# Hardwiring.net
KiCad netlist of a schematic drawn in Altium Designer
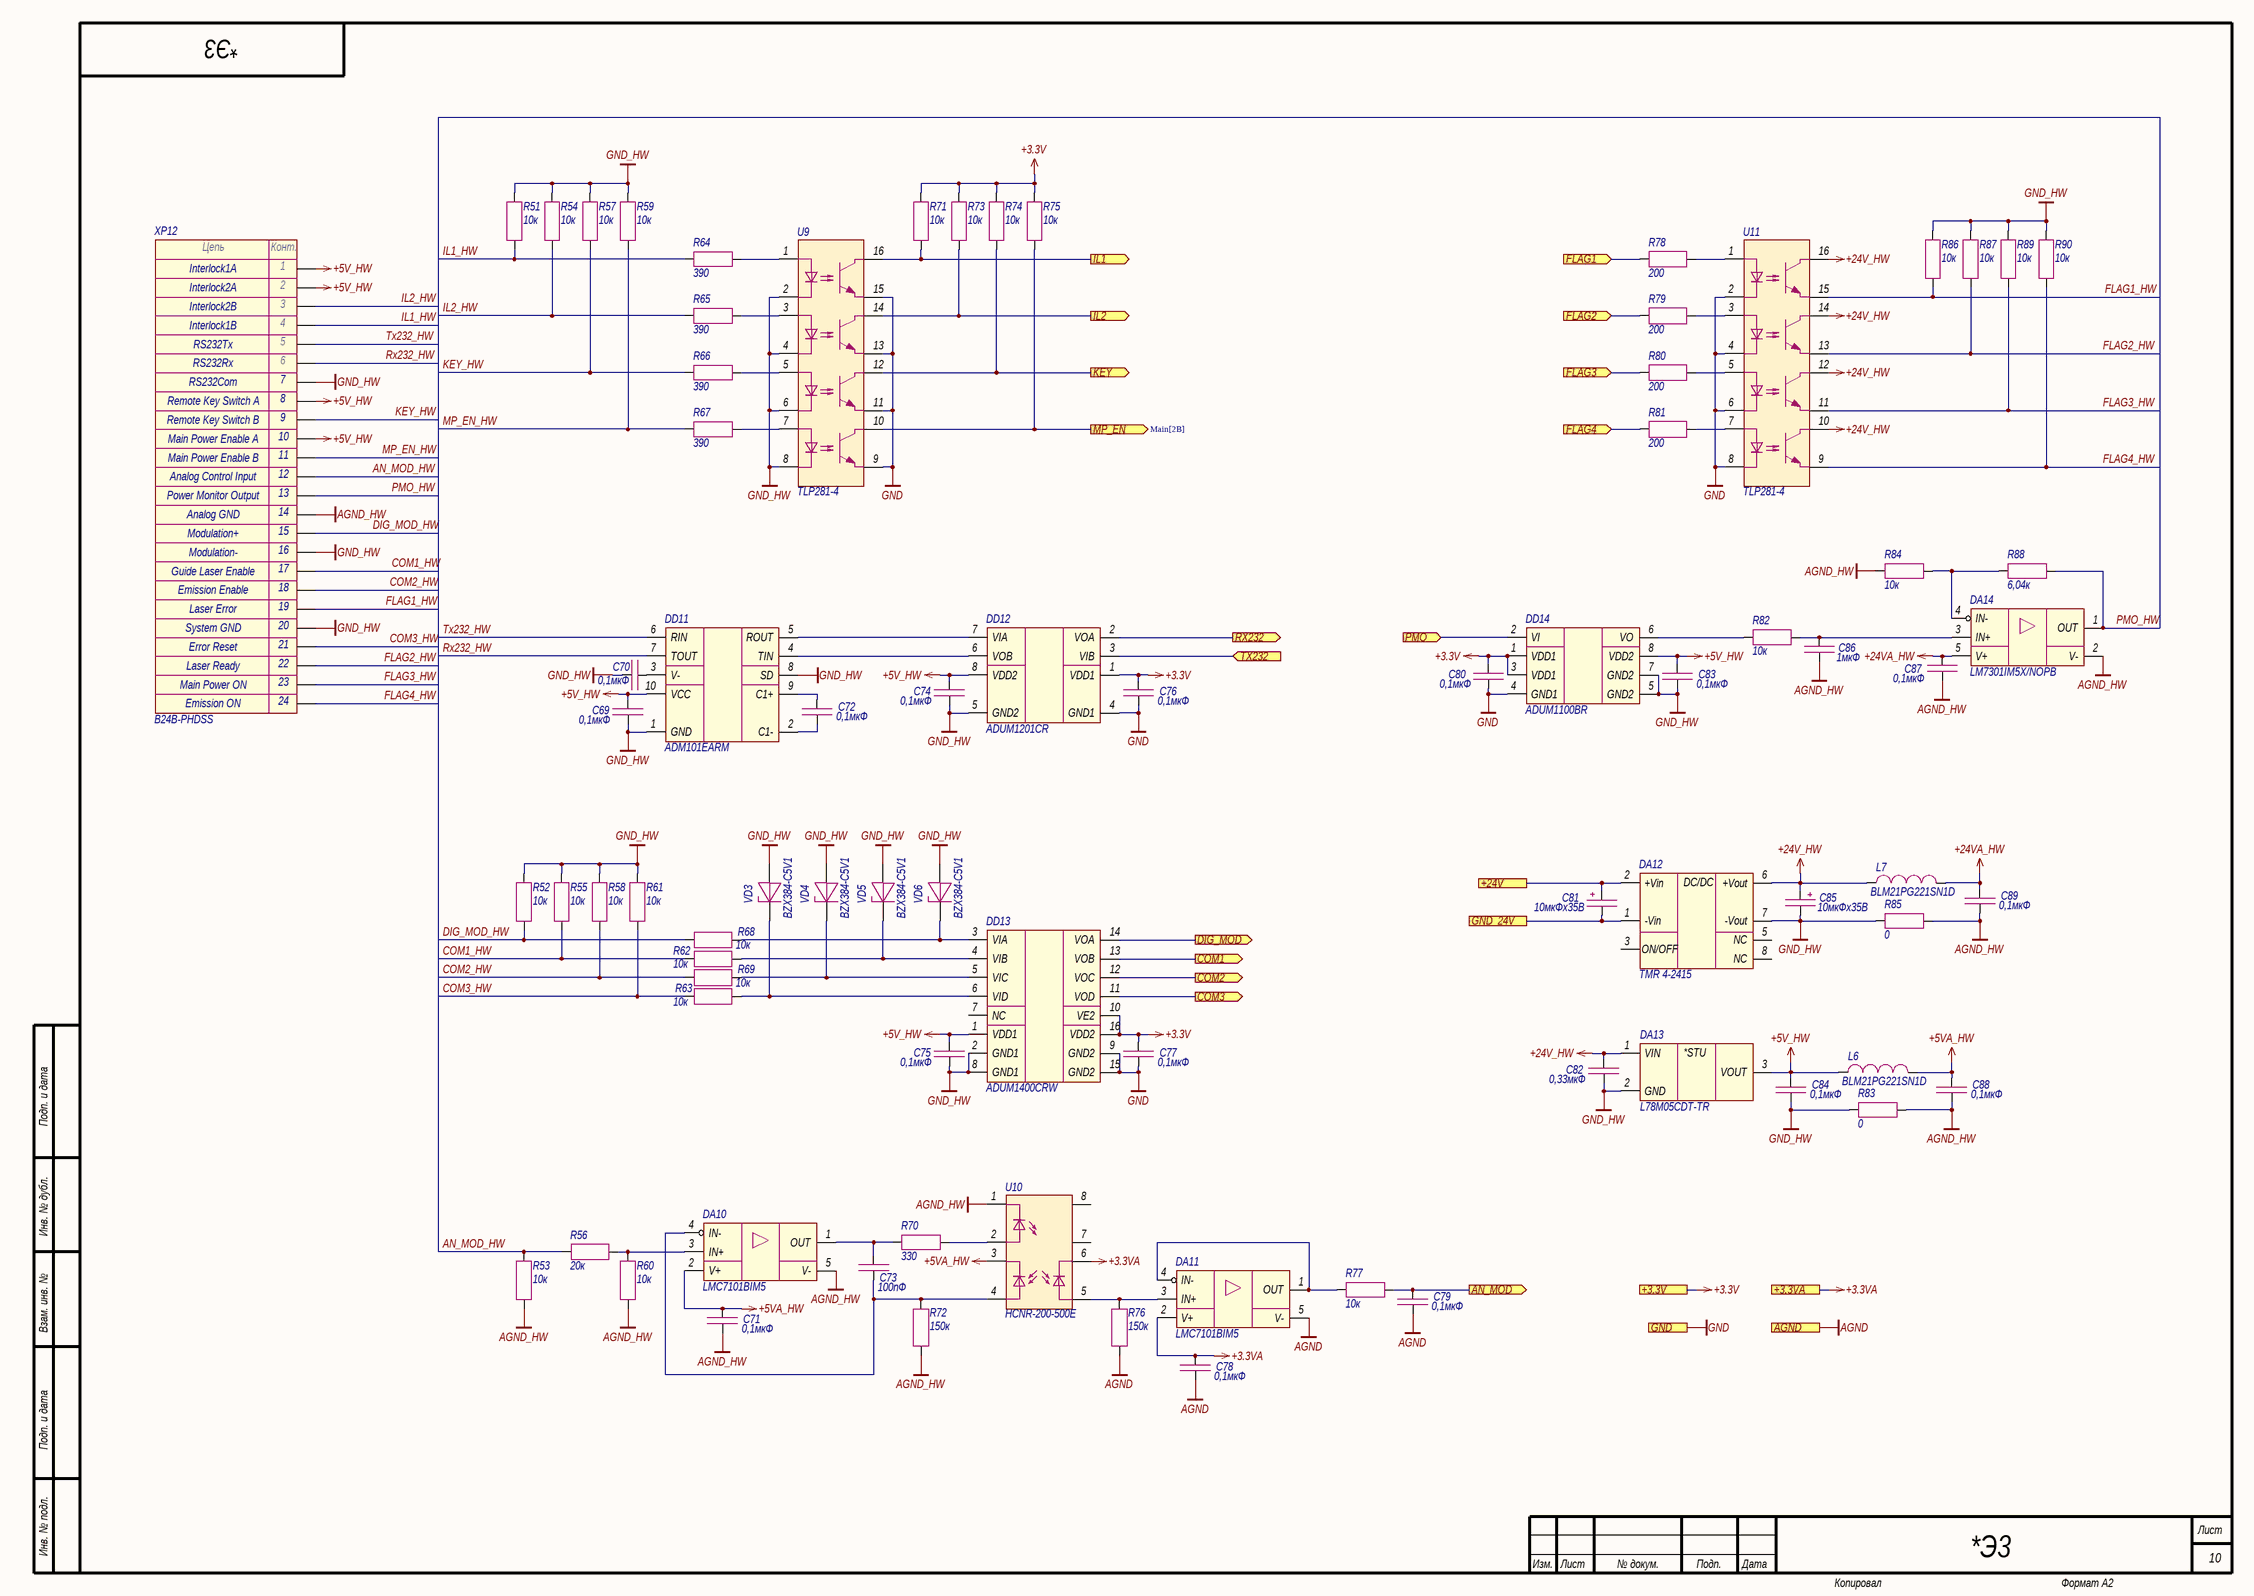
[diagram p0: Hardwiring.SchDoc]

(export (version "E")
  (design (tool "Eeschema 10.0.6"))
  (components
    (comp (ref "C69")
      (value "0,1мкФ")
      (footprint "Pcb_library:CAP_0603")
      (fields (field (name "MANUFACTURER") "Murata"))
      (libsource (lib "Schem_library") (part "Capacitor"))
    )
    (comp (ref "C70")
      (value "0,1мкФ")
      (footprint "Pcb_library:CAP_0603")
      (fields (field (name "MANUFACTURER") "Murata"))
      (libsource (lib "Schem_library") (part "Capacitor"))
    )
    (comp (ref "C71")
      (value "0,1мкФ")
      (footprint "Pcb_library:CAP_0603")
      (fields (field (name "MANUFACTURER") "Murata"))
      (libsource (lib "Schem_library") (part "Capacitor"))
    )
    (comp (ref "C72")
      (value "0,1мкФ")
      (footprint "Pcb_library:CAP_0603")
      (fields (field (name "MANUFACTURER") "Murata"))
      (libsource (lib "Schem_library") (part "Capacitor"))
    )
    (comp (ref "C73")
      (value "100пФ")
      (footprint "Pcb_library:CAP_0603")
      (fields (field (name "MANUFACTURER") "Murata"))
      (libsource (lib "Schem_library") (part "Capacitor"))
    )
    (comp (ref "C74")
      (value "0,1мкФ")
      (footprint "Pcb_library:CAP_0603")
      (fields (field (name "MANUFACTURER") "Murata"))
      (libsource (lib "Schem_library") (part "Capacitor"))
    )
    (comp (ref "C75")
      (value "0,1мкФ")
      (footprint "Pcb_library:CAP_0603")
      (fields (field (name "MANUFACTURER") "Murata"))
      (libsource (lib "Schem_library") (part "Capacitor"))
    )
    (comp (ref "C76")
      (value "0,1мкФ")
      (footprint "Pcb_library:CAP_0603")
      (fields (field (name "MANUFACTURER") "Murata"))
      (libsource (lib "Schem_library") (part "Capacitor"))
    )
    (comp (ref "C77")
      (value "0,1мкФ")
      (footprint "Pcb_library:CAP_0603")
      (fields (field (name "MANUFACTURER") "Murata"))
      (libsource (lib "Schem_library") (part "Capacitor"))
    )
    (comp (ref "C78")
      (value "0,1мкФ")
      (footprint "Pcb_library:CAP_0603")
      (fields (field (name "MANUFACTURER") "Murata"))
      (libsource (lib "Schem_library") (part "Capacitor"))
    )
    (comp (ref "C79")
      (value "0,1мкФ")
      (footprint "Pcb_library:CAP_0603")
      (fields (field (name "MANUFACTURER") "Murata"))
      (libsource (lib "Schem_library") (part "Capacitor"))
    )
    (comp (ref "C80")
      (value "0,1мкФ")
      (footprint "Pcb_library:CAP_0603")
      (fields (field (name "MANUFACTURER") "Murata"))
      (libsource (lib "Schem_library") (part "Capacitor"))
    )
    (comp (ref "C81")
      (value "10мкФх35B")
      (footprint "Pcb_library:CAP_C")
      (libsource (lib "Schem_library") (part "Capacitor_Polar"))
    )
    (comp (ref "C82")
      (value "0,33мкФ")
      (footprint "Pcb_library:CAP_0805")
      (fields (field (name "MANUFACTURER") "Murata"))
      (libsource (lib "Schem_library") (part "Capacitor"))
    )
    (comp (ref "C83")
      (value "0,1мкФ")
      (footprint "Pcb_library:CAP_0603")
      (fields (field (name "MANUFACTURER") "Murata"))
      (libsource (lib "Schem_library") (part "Capacitor"))
    )
    (comp (ref "C84")
      (value "0,1мкФ")
      (footprint "Pcb_library:CAP_0603")
      (fields (field (name "MANUFACTURER") "Murata"))
      (libsource (lib "Schem_library") (part "Capacitor"))
    )
    (comp (ref "C85")
      (value "10мкФх35B")
      (footprint "Pcb_library:CAP_C")
      (libsource (lib "Schem_library") (part "Capacitor_Polar"))
    )
    (comp (ref "C86")
      (value "1мкФ")
      (footprint "Pcb_library:CAP_0603")
      (fields (field (name "MANUFACTURER") "Murata"))
      (libsource (lib "Schem_library") (part "Capacitor"))
    )
    (comp (ref "C87")
      (value "0,1мкФ")
      (footprint "Pcb_library:CAP_0603")
      (fields (field (name "MANUFACTURER") "Murata"))
      (libsource (lib "Schem_library") (part "Capacitor"))
    )
    (comp (ref "C88")
      (value "0,1мкФ")
      (footprint "Pcb_library:CAP_0603")
      (fields (field (name "MANUFACTURER") "Murata"))
      (libsource (lib "Schem_library") (part "Capacitor"))
    )
    (comp (ref "C89")
      (value "0,1мкФ")
      (footprint "Pcb_library:CAP_0603")
      (fields (field (name "MANUFACTURER") "Murata"))
      (libsource (lib "Schem_library") (part "Capacitor"))
    )
    (comp (ref "DA10")
      (value "LMC7101BIM5")
      (footprint "Pcb_library:SOT-23-5")
      (fields (field (name "MANUFACTURER") "Texas Instruments"))
      (libsource (lib "Schem_library") (part "LMC7101"))
    )
    (comp (ref "DA11")
      (value "LMC7101BIM5")
      (footprint "Pcb_library:SOT-23-5")
      (fields (field (name "MANUFACTURER") "Texas Instruments"))
      (libsource (lib "Schem_library") (part "LMC7101"))
    )
    (comp (ref "DA12")
      (value "TMR 4-2415")
      (footprint "Pcb_library:TMR4 (SIP-8)")
      (fields (field (name "MANUFACTURER") "Traco Power"))
      (libsource (lib "Schem_library") (part "TMR4"))
    )
    (comp (ref "DA13")
      (value "L78M05CDT-TR")
      (footprint "Pcb_library:TO-252")
      (fields (field (name "MANUFACTURER") "STMicroelectronics"))
      (libsource (lib "Schem_library") (part "L78M"))
    )
    (comp (ref "DA14")
      (value "LM7301IM5X/NOPB")
      (footprint "Pcb_library:SOT-23-5")
      (fields (field (name "MANUFACTURER") "Texas Instruments"))
      (libsource (lib "Schem_library") (part "LM7301IM5"))
    )
    (comp (ref "DD11")
      (value "ADM101EARM")
      (footprint "Pcb_library:MSOP-10")
      (fields (field (name "MANUFACTURER") "Analog Devices"))
      (libsource (lib "Schem_library") (part "ADM101EARM"))
    )
    (comp (ref "DD12")
      (value "ADUM1201CR")
      (footprint "Pcb_library:SOIC-8")
      (fields (field (name "MANUFACTURER") "Analog Devices"))
      (libsource (lib "Schem_library") (part "ADUM1201"))
    )
    (comp (ref "DD13")
      (value "ADUM1400CRW")
      (footprint "Pcb_library:SOIC-16W")
      (fields (field (name "MANUFACTURER") "Analog Devices"))
      (libsource (lib "Schem_library") (part "ADUM1400"))
    )
    (comp (ref "DD14")
      (value "ADUM1100BR")
      (footprint "Pcb_library:SOIC-8")
      (fields (field (name "MANUFACTURER") "Analog Devices"))
      (libsource (lib "Schem_library") (part "ADUM1100"))
    )
    (comp (ref "L6")
      (value "BLM21PG221SN1D")
      (footprint "Pcb_library:IND_0805")
      (fields (field (name "MANUFACTURER") "Murata"))
      (libsource (lib "Schem_library") (part "Inductor"))
    )
    (comp (ref "L7")
      (value "BLM21PG221SN1D")
      (footprint "Pcb_library:IND_0805")
      (fields (field (name "MANUFACTURER") "Murata"))
      (libsource (lib "Schem_library") (part "Inductor"))
    )
    (comp (ref "R51")
      (value "10к")
      (footprint "Pcb_library:RES_0603")
      (fields (field (name "MANUFACTURER") "Yageo"))
      (libsource (lib "Schem_library") (part "Resistor"))
    )
    (comp (ref "R52")
      (value "10к")
      (footprint "Pcb_library:RES_0603")
      (fields (field (name "MANUFACTURER") "Yageo"))
      (libsource (lib "Schem_library") (part "Resistor"))
    )
    (comp (ref "R53")
      (value "10к")
      (footprint "Pcb_library:RES_0603")
      (fields (field (name "MANUFACTURER") "Yageo"))
      (libsource (lib "Schem_library") (part "Resistor"))
    )
    (comp (ref "R54")
      (value "10к")
      (footprint "Pcb_library:RES_0603")
      (fields (field (name "MANUFACTURER") "Yageo"))
      (libsource (lib "Schem_library") (part "Resistor"))
    )
    (comp (ref "R55")
      (value "10к")
      (footprint "Pcb_library:RES_0603")
      (fields (field (name "MANUFACTURER") "Yageo"))
      (libsource (lib "Schem_library") (part "Resistor"))
    )
    (comp (ref "R56")
      (value "20к")
      (footprint "Pcb_library:RES_0603")
      (fields (field (name "MANUFACTURER") "Yageo"))
      (libsource (lib "Schem_library") (part "Resistor"))
    )
    (comp (ref "R57")
      (value "10к")
      (footprint "Pcb_library:RES_0603")
      (fields (field (name "MANUFACTURER") "Yageo"))
      (libsource (lib "Schem_library") (part "Resistor"))
    )
    (comp (ref "R58")
      (value "10к")
      (footprint "Pcb_library:RES_0603")
      (fields (field (name "MANUFACTURER") "Yageo"))
      (libsource (lib "Schem_library") (part "Resistor"))
    )
    (comp (ref "R59")
      (value "10к")
      (footprint "Pcb_library:RES_0603")
      (fields (field (name "MANUFACTURER") "Yageo"))
      (libsource (lib "Schem_library") (part "Resistor"))
    )
    (comp (ref "R60")
      (value "10к")
      (footprint "Pcb_library:RES_0603")
      (fields (field (name "MANUFACTURER") "Yageo"))
      (libsource (lib "Schem_library") (part "Resistor"))
    )
    (comp (ref "R61")
      (value "10к")
      (footprint "Pcb_library:RES_0603")
      (fields (field (name "MANUFACTURER") "Yageo"))
      (libsource (lib "Schem_library") (part "Resistor"))
    )
    (comp (ref "R62")
      (value "10к")
      (footprint "Pcb_library:RES_0603")
      (fields (field (name "MANUFACTURER") "Yageo"))
      (libsource (lib "Schem_library") (part "Resistor"))
    )
    (comp (ref "R63")
      (value "10к")
      (footprint "Pcb_library:RES_0603")
      (fields (field (name "MANUFACTURER") "Yageo"))
      (libsource (lib "Schem_library") (part "Resistor"))
    )
    (comp (ref "R64")
      (value "390")
      (footprint "Pcb_library:RES_0603")
      (fields (field (name "MANUFACTURER") "Yageo"))
      (libsource (lib "Schem_library") (part "Resistor"))
    )
    (comp (ref "R65")
      (value "390")
      (footprint "Pcb_library:RES_0603")
      (fields (field (name "MANUFACTURER") "Yageo"))
      (libsource (lib "Schem_library") (part "Resistor"))
    )
    (comp (ref "R66")
      (value "390")
      (footprint "Pcb_library:RES_0603")
      (fields (field (name "MANUFACTURER") "Yageo"))
      (libsource (lib "Schem_library") (part "Resistor"))
    )
    (comp (ref "R67")
      (value "390")
      (footprint "Pcb_library:RES_0603")
      (fields (field (name "MANUFACTURER") "Yageo"))
      (libsource (lib "Schem_library") (part "Resistor"))
    )
    (comp (ref "R68")
      (value "10к")
      (footprint "Pcb_library:RES_0603")
      (fields (field (name "MANUFACTURER") "Yageo"))
      (libsource (lib "Schem_library") (part "Resistor"))
    )
    (comp (ref "R69")
      (value "10к")
      (footprint "Pcb_library:RES_0603")
      (fields (field (name "MANUFACTURER") "Yageo"))
      (libsource (lib "Schem_library") (part "Resistor"))
    )
    (comp (ref "R70")
      (value "330")
      (footprint "Pcb_library:RES_0603")
      (fields (field (name "MANUFACTURER") "Yageo"))
      (libsource (lib "Schem_library") (part "Resistor"))
    )
    (comp (ref "R71")
      (value "10к")
      (footprint "Pcb_library:RES_0603")
      (fields (field (name "MANUFACTURER") "Yageo"))
      (libsource (lib "Schem_library") (part "Resistor"))
    )
    (comp (ref "R72")
      (value "150к")
      (footprint "Pcb_library:RES_0603")
      (fields (field (name "MANUFACTURER") "Yageo"))
      (libsource (lib "Schem_library") (part "Resistor"))
    )
    (comp (ref "R73")
      (value "10к")
      (footprint "Pcb_library:RES_0603")
      (fields (field (name "MANUFACTURER") "Yageo"))
      (libsource (lib "Schem_library") (part "Resistor"))
    )
    (comp (ref "R74")
      (value "10к")
      (footprint "Pcb_library:RES_0603")
      (fields (field (name "MANUFACTURER") "Yageo"))
      (libsource (lib "Schem_library") (part "Resistor"))
    )
    (comp (ref "R75")
      (value "10к")
      (footprint "Pcb_library:RES_0603")
      (fields (field (name "MANUFACTURER") "Yageo"))
      (libsource (lib "Schem_library") (part "Resistor"))
    )
    (comp (ref "R76")
      (value "150к")
      (footprint "Pcb_library:RES_0603")
      (fields (field (name "MANUFACTURER") "Yageo"))
      (libsource (lib "Schem_library") (part "Resistor"))
    )
    (comp (ref "R77")
      (value "10к")
      (footprint "Pcb_library:RES_0603")
      (fields (field (name "MANUFACTURER") "Yageo"))
      (libsource (lib "Schem_library") (part "Resistor"))
    )
    (comp (ref "R78")
      (value "200")
      (footprint "Pcb_library:RES_0603")
      (fields (field (name "MANUFACTURER") "Yageo"))
      (libsource (lib "Schem_library") (part "Resistor"))
    )
    (comp (ref "R79")
      (value "200")
      (footprint "Pcb_library:RES_0603")
      (fields (field (name "MANUFACTURER") "Yageo"))
      (libsource (lib "Schem_library") (part "Resistor"))
    )
    (comp (ref "R80")
      (value "200")
      (footprint "Pcb_library:RES_0603")
      (fields (field (name "MANUFACTURER") "Yageo"))
      (libsource (lib "Schem_library") (part "Resistor"))
    )
    (comp (ref "R81")
      (value "200")
      (footprint "Pcb_library:RES_0603")
      (fields (field (name "MANUFACTURER") "Yageo"))
      (libsource (lib "Schem_library") (part "Resistor"))
    )
    (comp (ref "R82")
      (value "10к")
      (footprint "Pcb_library:RES_0603")
      (fields (field (name "MANUFACTURER") "Yageo"))
      (libsource (lib "Schem_library") (part "Resistor"))
    )
    (comp (ref "R83")
      (value "0")
      (footprint "Pcb_library:RES_0805")
      (fields (field (name "MANUFACTURER") "Yageo"))
      (libsource (lib "Schem_library") (part "Resistor"))
    )
    (comp (ref "R84")
      (value "10к")
      (footprint "Pcb_library:RES_0603")
      (fields (field (name "MANUFACTURER") "Yageo"))
      (libsource (lib "Schem_library") (part "Resistor"))
    )
    (comp (ref "R85")
      (value "0")
      (footprint "Pcb_library:RES_0805")
      (fields (field (name "MANUFACTURER") "Yageo"))
      (libsource (lib "Schem_library") (part "Resistor"))
    )
    (comp (ref "R86")
      (value "10к")
      (footprint "Pcb_library:RES_0603")
      (fields (field (name "MANUFACTURER") "Yageo"))
      (libsource (lib "Schem_library") (part "Resistor"))
    )
    (comp (ref "R87")
      (value "10к")
      (footprint "Pcb_library:RES_0603")
      (fields (field (name "MANUFACTURER") "Yageo"))
      (libsource (lib "Schem_library") (part "Resistor"))
    )
    (comp (ref "R88")
      (value "6,04к")
      (footprint "Pcb_library:RES_0603")
      (fields (field (name "MANUFACTURER") "Yageo"))
      (libsource (lib "Schem_library") (part "Resistor"))
    )
    (comp (ref "R89")
      (value "10к")
      (footprint "Pcb_library:RES_0603")
      (fields (field (name "MANUFACTURER") "Yageo"))
      (libsource (lib "Schem_library") (part "Resistor"))
    )
    (comp (ref "R90")
      (value "10к")
      (footprint "Pcb_library:RES_0603")
      (fields (field (name "MANUFACTURER") "Yageo"))
      (libsource (lib "Schem_library") (part "Resistor"))
    )
    (comp (ref "U9")
      (value "TLP281-4")
      (footprint "Pcb_library:SOP-16")
      (fields (field (name "MANUFACTURER") "Toshiba"))
      (libsource (lib "Schem_library") (part "TLP281-4"))
    )
    (comp (ref "U10")
      (value "HCNR-200-500E")
      (footprint "Pcb_library:HCNR200")
      (fields (field (name "MANUFACTURER") "Avago"))
      (libsource (lib "Schem_library") (part "HCNR200"))
    )
    (comp (ref "U11")
      (value "TLP281-4")
      (footprint "Pcb_library:SOP-16")
      (fields (field (name "MANUFACTURER") "Toshiba"))
      (libsource (lib "Schem_library") (part "TLP281-4"))
    )
    (comp (ref "VD3")
      (value "BZX384-C5V1")
      (footprint "Pcb_library:SOD-323")
      (fields (field (name "MANUFACTURER") "Nexperia"))
      (libsource (lib "Schem_library") (part "Diode_Zener"))
    )
    (comp (ref "VD4")
      (value "BZX384-C5V1")
      (footprint "Pcb_library:SOD-323")
      (fields (field (name "MANUFACTURER") "Nexperia"))
      (libsource (lib "Schem_library") (part "Diode_Zener"))
    )
    (comp (ref "VD5")
      (value "BZX384-C5V1")
      (footprint "Pcb_library:SOD-323")
      (fields (field (name "MANUFACTURER") "Nexperia"))
      (libsource (lib "Schem_library") (part "Diode_Zener"))
    )
    (comp (ref "VD6")
      (value "BZX384-C5V1")
      (footprint "Pcb_library:SOD-323")
      (fields (field (name "MANUFACTURER") "Nexperia"))
      (libsource (lib "Schem_library") (part "Diode_Zener"))
    )
    (comp (ref "XP12")
      (value "B24B-PHDSS")
      (footprint "Pcb_library:B24B-PHDSS")
      (fields (field (name "MANUFACTURER") "JST"))
      (libsource (lib "Schem_library") (part "Connector-24"))
    )
  )
  (nets
    (net (code "1") (name "+3.3V") (class "Default")
      (node (ref "C76") (pin "1") (pinfunction "1_1") (pintype "passive"))
      (node (ref "C77") (pin "1") (pinfunction "1_1") (pintype "passive"))
      (node (ref "C80") (pin "1") (pinfunction "1_1") (pintype "passive"))
      (node (ref "DD12") (pin "1") (pinfunction "VDD1_1") (pintype "passive"))
      (node (ref "DD13") (pin "10") (pinfunction "VE2_10") (pintype "passive"))
      (node (ref "DD13") (pin "16") (pinfunction "VDD2_16") (pintype "passive"))
      (node (ref "DD14") (pin "1") (pinfunction "VDD1_1") (pintype "passive"))
      (node (ref "DD14") (pin "3") (pinfunction "VDD1_3") (pintype "passive"))
      (node (ref "R71") (pin "1") (pinfunction "1_1") (pintype "passive"))
      (node (ref "R73") (pin "1") (pinfunction "1_1") (pintype "passive"))
      (node (ref "R74") (pin "1") (pinfunction "1_1") (pintype "passive"))
      (node (ref "R75") (pin "1") (pinfunction "1_1") (pintype "passive"))
    )
    (net (code "2") (name "+3.3VA") (class "Default")
      (node (ref "C78") (pin "1") (pinfunction "1_1") (pintype "passive"))
      (node (ref "DA11") (pin "2") (pinfunction "V+_2") (pintype "passive"))
      (node (ref "U10") (pin "6") (pintype "passive"))
    )
    (net (code "3") (name "+5VA_HW") (class "Default")
      (node (ref "C71") (pin "1") (pinfunction "1_1") (pintype "passive"))
      (node (ref "C88") (pin "1") (pinfunction "1_1") (pintype "passive"))
      (node (ref "DA10") (pin "2") (pinfunction "V+_2") (pintype "passive"))
      (node (ref "L6") (pin "2") (pinfunction "2_2") (pintype "passive"))
      (node (ref "U10") (pin "3") (pintype "passive"))
    )
    (net (code "4") (name "+5V_HW") (class "Default")
      (node (ref "C69") (pin "1") (pinfunction "1_1") (pintype "passive"))
      (node (ref "C74") (pin "1") (pinfunction "1_1") (pintype "passive"))
      (node (ref "C75") (pin "1") (pinfunction "1_1") (pintype "passive"))
      (node (ref "C83") (pin "1") (pinfunction "1_1") (pintype "passive"))
      (node (ref "C84") (pin "1") (pinfunction "1_1") (pintype "passive"))
      (node (ref "DA13") (pin "3") (pinfunction "VOUT_3") (pintype "passive"))
      (node (ref "DD11") (pin "10") (pinfunction "VCC_10") (pintype "passive"))
      (node (ref "DD12") (pin "8") (pinfunction "VDD2_8") (pintype "passive"))
      (node (ref "DD13") (pin "1") (pinfunction "VDD1_1") (pintype "passive"))
      (node (ref "DD14") (pin "8") (pinfunction "VDD2_8") (pintype "passive"))
      (node (ref "L6") (pin "1") (pinfunction "1_1") (pintype "passive"))
      (node (ref "XP12") (pin "1") (pintype "passive"))
      (node (ref "XP12") (pin "10") (pintype "passive"))
      (node (ref "XP12") (pin "2") (pintype "passive"))
      (node (ref "XP12") (pin "8") (pintype "passive"))
    )
    (net (code "5") (name "+24VA_HW") (class "Default")
      (node (ref "C87") (pin "1") (pinfunction "1_1") (pintype "passive"))
      (node (ref "C89") (pin "1") (pinfunction "1_1") (pintype "passive"))
      (node (ref "DA14") (pin "5") (pinfunction "V+_5") (pintype "passive"))
      (node (ref "L7") (pin "2") (pinfunction "2_2") (pintype "passive"))
    )
    (net (code "6") (name "+24V_HW") (class "Default")
      (node (ref "C82") (pin "2") (pinfunction "2_2") (pintype "passive"))
      (node (ref "C85") (pin "1") (pinfunction "1_1") (pintype "passive"))
      (node (ref "DA12") (pin "6") (pinfunction "+Vout_6") (pintype "passive"))
      (node (ref "DA13") (pin "1") (pinfunction "VIN_1") (pintype "passive"))
      (node (ref "L7") (pin "1") (pinfunction "1_1") (pintype "passive"))
      (node (ref "U11") (pin "10") (pintype "passive"))
      (node (ref "U11") (pin "12") (pintype "passive"))
      (node (ref "U11") (pin "14") (pintype "passive"))
      (node (ref "U11") (pin "16") (pintype "passive"))
    )
    (net (code "7") (name "/+24V") (class "Default")
      (node (ref "C81") (pin "1") (pinfunction "1_1") (pintype "passive"))
      (node (ref "DA12") (pin "2") (pinfunction "+Vin_2") (pintype "passive"))
    )
    (net (code "8") (name "/AN_MOD") (class "Default")
      (node (ref "C79") (pin "1") (pinfunction "1_1") (pintype "passive"))
      (node (ref "R77") (pin "2") (pinfunction "2_2") (pintype "passive"))
    )
    (net (code "9") (name "/AN_MOD_HW") (class "Default")
      (node (ref "R53") (pin "1") (pinfunction "1_1") (pintype "passive"))
      (node (ref "R56") (pin "1") (pinfunction "1_1") (pintype "passive"))
      (node (ref "XP12") (pin "12") (pintype "passive"))
    )
    (net (code "10") (name "/COM1") (class "Default")
      (node (ref "DD13") (pin "13") (pinfunction "VOB_13") (pintype "passive"))
    )
    (net (code "11") (name "/COM1_HW") (class "Default")
      (node (ref "R55") (pin "2") (pinfunction "2_2") (pintype "passive"))
      (node (ref "R62") (pin "1") (pinfunction "1_1") (pintype "passive"))
      (node (ref "XP12") (pin "17") (pintype "passive"))
    )
    (net (code "12") (name "/COM2") (class "Default")
      (node (ref "DD13") (pin "12") (pinfunction "VOC_12") (pintype "passive"))
    )
    (net (code "13") (name "/COM2_HW") (class "Default")
      (node (ref "R58") (pin "2") (pinfunction "2_2") (pintype "passive"))
      (node (ref "R69") (pin "1") (pinfunction "1_1") (pintype "passive"))
      (node (ref "XP12") (pin "18") (pintype "passive"))
    )
    (net (code "14") (name "/COM3") (class "Default")
      (node (ref "DD13") (pin "11") (pinfunction "VOD_11") (pintype "passive"))
    )
    (net (code "15") (name "/COM3_HW") (class "Default")
      (node (ref "R61") (pin "2") (pinfunction "2_2") (pintype "passive"))
      (node (ref "R63") (pin "1") (pinfunction "1_1") (pintype "passive"))
      (node (ref "XP12") (pin "21") (pintype "passive"))
    )
    (net (code "16") (name "/DIG_MOD") (class "Default")
      (node (ref "DD13") (pin "14") (pinfunction "VOA_14") (pintype "passive"))
    )
    (net (code "17") (name "/DIG_MOD_HW") (class "Default")
      (node (ref "R52") (pin "2") (pinfunction "2_2") (pintype "passive"))
      (node (ref "R68") (pin "1") (pinfunction "1_1") (pintype "passive"))
      (node (ref "XP12") (pin "15") (pintype "passive"))
    )
    (net (code "18") (name "/FLAG1") (class "Default")
      (node (ref "R78") (pin "2") (pinfunction "2_2") (pintype "passive"))
    )
    (net (code "19") (name "/FLAG1_HW") (class "Default")
      (node (ref "R86") (pin "2") (pinfunction "2_2") (pintype "passive"))
      (node (ref "U11") (pin "15") (pintype "passive"))
      (node (ref "XP12") (pin "19") (pintype "passive"))
    )
    (net (code "20") (name "/FLAG2") (class "Default")
      (node (ref "R79") (pin "2") (pinfunction "2_2") (pintype "passive"))
    )
    (net (code "21") (name "/FLAG2_HW") (class "Default")
      (node (ref "R87") (pin "2") (pinfunction "2_2") (pintype "passive"))
      (node (ref "U11") (pin "13") (pintype "passive"))
      (node (ref "XP12") (pin "22") (pintype "passive"))
    )
    (net (code "22") (name "/FLAG3") (class "Default")
      (node (ref "R80") (pin "2") (pinfunction "2_2") (pintype "passive"))
    )
    (net (code "23") (name "/FLAG3_HW") (class "Default")
      (node (ref "R89") (pin "2") (pinfunction "2_2") (pintype "passive"))
      (node (ref "U11") (pin "11") (pintype "passive"))
      (node (ref "XP12") (pin "23") (pintype "passive"))
    )
    (net (code "24") (name "/FLAG4") (class "Default")
      (node (ref "R81") (pin "2") (pinfunction "2_2") (pintype "passive"))
    )
    (net (code "25") (name "/FLAG4_HW") (class "Default")
      (node (ref "R90") (pin "2") (pinfunction "2_2") (pintype "passive"))
      (node (ref "U11") (pin "9") (pintype "passive"))
      (node (ref "XP12") (pin "24") (pintype "passive"))
    )
    (net (code "26") (name "/GND_24V") (class "Default")
      (node (ref "C81") (pin "2") (pinfunction "2_2") (pintype "passive"))
      (node (ref "DA12") (pin "1") (pinfunction "-Vin_1") (pintype "passive"))
    )
    (net (code "27") (name "/IL1") (class "Default")
      (node (ref "R71") (pin "2") (pinfunction "2_2") (pintype "passive"))
      (node (ref "U9") (pin "16") (pintype "passive"))
    )
    (net (code "28") (name "/IL1_HW") (class "Default")
      (node (ref "R51") (pin "2") (pinfunction "2_2") (pintype "passive"))
      (node (ref "R64") (pin "1") (pinfunction "1_1") (pintype "passive"))
      (node (ref "XP12") (pin "4") (pintype "passive"))
    )
    (net (code "29") (name "/IL2") (class "Default")
      (node (ref "R73") (pin "2") (pinfunction "2_2") (pintype "passive"))
      (node (ref "U9") (pin "14") (pintype "passive"))
    )
    (net (code "30") (name "/IL2_HW") (class "Default")
      (node (ref "R54") (pin "2") (pinfunction "2_2") (pintype "passive"))
      (node (ref "R65") (pin "1") (pinfunction "1_1") (pintype "passive"))
      (node (ref "XP12") (pin "3") (pintype "passive"))
    )
    (net (code "31") (name "/KEY") (class "Default")
      (node (ref "R74") (pin "2") (pinfunction "2_2") (pintype "passive"))
      (node (ref "U9") (pin "12") (pintype "passive"))
    )
    (net (code "32") (name "/KEY_HW") (class "Default")
      (node (ref "R57") (pin "2") (pinfunction "2_2") (pintype "passive"))
      (node (ref "R66") (pin "1") (pinfunction "1_1") (pintype "passive"))
      (node (ref "XP12") (pin "9") (pintype "passive"))
    )
    (net (code "33") (name "/MP_EN") (class "Default")
      (node (ref "R75") (pin "2") (pinfunction "2_2") (pintype "passive"))
      (node (ref "U9") (pin "10") (pintype "passive"))
    )
    (net (code "34") (name "/MP_EN_HW") (class "Default")
      (node (ref "R59") (pin "2") (pinfunction "2_2") (pintype "passive"))
      (node (ref "R67") (pin "1") (pinfunction "1_1") (pintype "passive"))
      (node (ref "XP12") (pin "11") (pintype "passive"))
    )
    (net (code "35") (name "/PMO") (class "Default")
      (node (ref "DD14") (pin "2") (pinfunction "VI_2") (pintype "passive"))
    )
    (net (code "36") (name "/PMO_HW") (class "Default")
      (node (ref "DA14") (pin "1") (pinfunction "OUT_1") (pintype "passive"))
      (node (ref "R88") (pin "2") (pinfunction "2_2") (pintype "passive"))
      (node (ref "XP12") (pin "13") (pintype "passive"))
    )
    (net (code "37") (name "/RX232") (class "Default")
      (node (ref "DD12") (pin "2") (pinfunction "VOA_2") (pintype "passive"))
    )
    (net (code "38") (name "/Rx232_HW") (class "Default")
      (node (ref "DD11") (pin "7") (pinfunction "TOUT_7") (pintype "passive"))
      (node (ref "XP12") (pin "6") (pintype "passive"))
    )
    (net (code "39") (name "/TX232") (class "Default")
      (node (ref "DD12") (pin "3") (pinfunction "VIB_3") (pintype "passive"))
    )
    (net (code "40") (name "/Tx232_HW") (class "Default")
      (node (ref "DD11") (pin "6") (pinfunction "RIN_6") (pintype "passive"))
      (node (ref "XP12") (pin "5") (pintype "passive"))
    )
    (net (code "41") (name "AGND") (class "Default")
      (node (ref "C78") (pin "2") (pinfunction "2_2") (pintype "passive"))
      (node (ref "C79") (pin "2") (pinfunction "2_2") (pintype "passive"))
      (node (ref "DA11") (pin "5") (pinfunction "V-_5") (pintype "passive"))
      (node (ref "R76") (pin "2") (pinfunction "2_2") (pintype "passive"))
    )
    (net (code "42") (name "AGND_HW") (class "Default")
      (node (ref "C71") (pin "2") (pinfunction "2_2") (pintype "passive"))
      (node (ref "C86") (pin "2") (pinfunction "2_2") (pintype "passive"))
      (node (ref "C87") (pin "2") (pinfunction "2_2") (pintype "passive"))
      (node (ref "C88") (pin "2") (pinfunction "2_2") (pintype "passive"))
      (node (ref "C89") (pin "2") (pinfunction "2_2") (pintype "passive"))
      (node (ref "DA10") (pin "5") (pinfunction "V-_5") (pintype "passive"))
      (node (ref "DA14") (pin "2") (pinfunction "V-_2") (pintype "passive"))
      (node (ref "R53") (pin "2") (pinfunction "2_2") (pintype "passive"))
      (node (ref "R60") (pin "2") (pinfunction "2_2") (pintype "passive"))
      (node (ref "R72") (pin "2") (pinfunction "2_2") (pintype "passive"))
      (node (ref "R83") (pin "2") (pinfunction "2_2") (pintype "passive"))
      (node (ref "R84") (pin "1") (pinfunction "1_1") (pintype "passive"))
      (node (ref "R85") (pin "2") (pinfunction "2_2") (pintype "passive"))
      (node (ref "U10") (pin "1") (pintype "passive"))
      (node (ref "XP12") (pin "14") (pintype "passive"))
    )
    (net (code "43") (name "GND") (class "Default")
      (node (ref "C76") (pin "2") (pinfunction "2_2") (pintype "passive"))
      (node (ref "C77") (pin "2") (pinfunction "2_2") (pintype "passive"))
      (node (ref "C80") (pin "2") (pinfunction "2_2") (pintype "passive"))
      (node (ref "DD12") (pin "4") (pinfunction "GND1_4") (pintype "passive"))
      (node (ref "DD13") (pin "15") (pinfunction "GND2_15") (pintype "passive"))
      (node (ref "DD13") (pin "9") (pinfunction "GND2_9") (pintype "passive"))
      (node (ref "DD14") (pin "4") (pinfunction "GND1_4") (pintype "passive"))
      (node (ref "U11") (pin "2") (pintype "passive"))
      (node (ref "U11") (pin "4") (pintype "passive"))
      (node (ref "U11") (pin "6") (pintype "passive"))
      (node (ref "U11") (pin "8") (pintype "passive"))
      (node (ref "U9") (pin "11") (pintype "passive"))
      (node (ref "U9") (pin "13") (pintype "passive"))
      (node (ref "U9") (pin "15") (pintype "passive"))
      (node (ref "U9") (pin "9") (pintype "passive"))
    )
    (net (code "44") (name "GND_HW") (class "Default")
      (node (ref "C69") (pin "2") (pinfunction "2_2") (pintype "passive"))
      (node (ref "C70") (pin "2") (pinfunction "2_2") (pintype "passive"))
      (node (ref "C74") (pin "2") (pinfunction "2_2") (pintype "passive"))
      (node (ref "C75") (pin "2") (pinfunction "2_2") (pintype "passive"))
      (node (ref "C82") (pin "1") (pinfunction "1_1") (pintype "passive"))
      (node (ref "C83") (pin "2") (pinfunction "2_2") (pintype "passive"))
      (node (ref "C84") (pin "2") (pinfunction "2_2") (pintype "passive"))
      (node (ref "C85") (pin "2") (pinfunction "2_2") (pintype "passive"))
      (node (ref "DA12") (pin "7") (pinfunction "-Vout_7") (pintype "passive"))
      (node (ref "DA13") (pin "2") (pinfunction "GND_2") (pintype "passive"))
      (node (ref "DD11") (pin "1") (pinfunction "GND_1") (pintype "passive"))
      (node (ref "DD11") (pin "8") (pinfunction "SD_8") (pintype "passive"))
      (node (ref "DD12") (pin "5") (pinfunction "GND2_5") (pintype "passive"))
      (node (ref "DD13") (pin "2") (pinfunction "GND1_2") (pintype "passive"))
      (node (ref "DD13") (pin "8") (pinfunction "GND1_8") (pintype "passive"))
      (node (ref "DD14") (pin "5") (pinfunction "GND2_5") (pintype "passive"))
      (node (ref "DD14") (pin "7") (pinfunction "GND2_7") (pintype "passive"))
      (node (ref "R51") (pin "1") (pinfunction "1_1") (pintype "passive"))
      (node (ref "R52") (pin "1") (pinfunction "1_1") (pintype "passive"))
      (node (ref "R54") (pin "1") (pinfunction "1_1") (pintype "passive"))
      (node (ref "R55") (pin "1") (pinfunction "1_1") (pintype "passive"))
      (node (ref "R57") (pin "1") (pinfunction "1_1") (pintype "passive"))
      (node (ref "R58") (pin "1") (pinfunction "1_1") (pintype "passive"))
      (node (ref "R59") (pin "1") (pinfunction "1_1") (pintype "passive"))
      (node (ref "R61") (pin "1") (pinfunction "1_1") (pintype "passive"))
      (node (ref "R83") (pin "1") (pinfunction "1_1") (pintype "passive"))
      (node (ref "R85") (pin "1") (pinfunction "1_1") (pintype "passive"))
      (node (ref "R86") (pin "1") (pinfunction "1_1") (pintype "passive"))
      (node (ref "R87") (pin "1") (pinfunction "1_1") (pintype "passive"))
      (node (ref "R89") (pin "1") (pinfunction "1_1") (pintype "passive"))
      (node (ref "R90") (pin "1") (pinfunction "1_1") (pintype "passive"))
      (node (ref "U9") (pin "2") (pintype "passive"))
      (node (ref "U9") (pin "4") (pintype "passive"))
      (node (ref "U9") (pin "6") (pintype "passive"))
      (node (ref "U9") (pin "8") (pintype "passive"))
      (node (ref "VD3") (pin "2") (pinfunction "A_2") (pintype "passive"))
      (node (ref "VD4") (pin "2") (pinfunction "A_2") (pintype "passive"))
      (node (ref "VD5") (pin "2") (pinfunction "A_2") (pintype "passive"))
      (node (ref "VD6") (pin "2") (pinfunction "A_2") (pintype "passive"))
      (node (ref "XP12") (pin "16") (pintype "passive"))
      (node (ref "XP12") (pin "20") (pintype "passive"))
      (node (ref "XP12") (pin "7") (pintype "passive"))
    )
    (net (code "45") (name "Net-(DA10-IN+)") (class "Default")
      (node (ref "DA10") (pin "3") (pinfunction "IN+_3") (pintype "passive"))
      (node (ref "R56") (pin "2") (pinfunction "2_2") (pintype "passive"))
      (node (ref "R60") (pin "1") (pinfunction "1_1") (pintype "passive"))
    )
    (net (code "46") (name "Net-(DA10-IN-)") (class "Default")
      (node (ref "C73") (pin "2") (pinfunction "2_2") (pintype "passive"))
      (node (ref "DA10") (pin "4") (pinfunction "IN-_4") (pintype "passive"))
      (node (ref "R72") (pin "1") (pinfunction "1_1") (pintype "passive"))
      (node (ref "U10") (pin "4") (pintype "passive"))
    )
    (net (code "47") (name "Net-(DA10-OUT)") (class "Default")
      (node (ref "C73") (pin "1") (pinfunction "1_1") (pintype "passive"))
      (node (ref "DA10") (pin "1") (pinfunction "OUT_1") (pintype "passive"))
      (node (ref "R70") (pin "1") (pinfunction "1_1") (pintype "passive"))
    )
    (net (code "48") (name "Net-(DA11-IN+)") (class "Default")
      (node (ref "DA11") (pin "3") (pinfunction "IN+_3") (pintype "passive"))
      (node (ref "R76") (pin "1") (pinfunction "1_1") (pintype "passive"))
      (node (ref "U10") (pin "5") (pintype "passive"))
    )
    (net (code "49") (name "Net-(DA11-IN-)") (class "Default")
      (node (ref "DA11") (pin "1") (pinfunction "OUT_1") (pintype "passive"))
      (node (ref "DA11") (pin "4") (pinfunction "IN-_4") (pintype "passive"))
      (node (ref "R77") (pin "1") (pinfunction "1_1") (pintype "passive"))
    )
    (net (code "50") (name "Net-(DA14-IN+)") (class "Default")
      (node (ref "C86") (pin "1") (pinfunction "1_1") (pintype "passive"))
      (node (ref "DA14") (pin "3") (pinfunction "IN+_3") (pintype "passive"))
      (node (ref "R82") (pin "2") (pinfunction "2_2") (pintype "passive"))
    )
    (net (code "51") (name "Net-(DA14-IN-)") (class "Default")
      (node (ref "DA14") (pin "4") (pinfunction "IN-_4") (pintype "passive"))
      (node (ref "R84") (pin "2") (pinfunction "2_2") (pintype "passive"))
      (node (ref "R88") (pin "1") (pinfunction "1_1") (pintype "passive"))
    )
    (net (code "52") (name "Net-(DD11-C1+)") (class "Default")
      (node (ref "C72") (pin "1") (pinfunction "1_1") (pintype "passive"))
      (node (ref "DD11") (pin "9") (pinfunction "C1+_9") (pintype "passive"))
    )
    (net (code "53") (name "Net-(DD11-C1-)") (class "Default")
      (node (ref "C72") (pin "2") (pinfunction "2_2") (pintype "passive"))
      (node (ref "DD11") (pin "2") (pinfunction "C1-_2") (pintype "passive"))
    )
    (net (code "54") (name "Net-(DD11-ROUT)") (class "Default")
      (node (ref "DD11") (pin "5") (pinfunction "ROUT_5") (pintype "passive"))
      (node (ref "DD12") (pin "7") (pinfunction "VIA_7") (pintype "passive"))
    )
    (net (code "55") (name "Net-(DD11-TIN)") (class "Default")
      (node (ref "DD11") (pin "4") (pinfunction "TIN_4") (pintype "passive"))
      (node (ref "DD12") (pin "6") (pinfunction "VOB_6") (pintype "passive"))
    )
    (net (code "56") (name "Net-(DD11-V-)") (class "Default")
      (node (ref "C70") (pin "1") (pinfunction "1_1") (pintype "passive"))
      (node (ref "DD11") (pin "3") (pinfunction "V-_3") (pintype "passive"))
    )
    (net (code "57") (name "Net-(DD13-VIA)") (class "Default")
      (node (ref "DD13") (pin "3") (pinfunction "VIA_3") (pintype "passive"))
      (node (ref "R68") (pin "2") (pinfunction "2_2") (pintype "passive"))
      (node (ref "VD6") (pin "1") (pinfunction "K_1") (pintype "passive"))
    )
    (net (code "58") (name "Net-(DD13-VIB)") (class "Default")
      (node (ref "DD13") (pin "4") (pinfunction "VIB_4") (pintype "passive"))
      (node (ref "R62") (pin "2") (pinfunction "2_2") (pintype "passive"))
      (node (ref "VD5") (pin "1") (pinfunction "K_1") (pintype "passive"))
    )
    (net (code "59") (name "Net-(DD13-VIC)") (class "Default")
      (node (ref "DD13") (pin "5") (pinfunction "VIC_5") (pintype "passive"))
      (node (ref "R69") (pin "2") (pinfunction "2_2") (pintype "passive"))
      (node (ref "VD4") (pin "1") (pinfunction "K_1") (pintype "passive"))
    )
    (net (code "60") (name "Net-(DD13-VID)") (class "Default")
      (node (ref "DD13") (pin "6") (pinfunction "VID_6") (pintype "passive"))
      (node (ref "R63") (pin "2") (pinfunction "2_2") (pintype "passive"))
      (node (ref "VD3") (pin "1") (pinfunction "K_1") (pintype "passive"))
    )
    (net (code "61") (name "Net-(DD14-VO)") (class "Default")
      (node (ref "DD14") (pin "6") (pinfunction "VO_6") (pintype "passive"))
      (node (ref "R82") (pin "1") (pinfunction "1_1") (pintype "passive"))
    )
    (net (code "62") (name "Net-(R64-Pad2)") (class "Default")
      (node (ref "R64") (pin "2") (pinfunction "2_2") (pintype "passive"))
      (node (ref "U9") (pin "1") (pintype "passive"))
    )
    (net (code "63") (name "Net-(R65-Pad2)") (class "Default")
      (node (ref "R65") (pin "2") (pinfunction "2_2") (pintype "passive"))
      (node (ref "U9") (pin "3") (pintype "passive"))
    )
    (net (code "64") (name "Net-(R66-Pad2)") (class "Default")
      (node (ref "R66") (pin "2") (pinfunction "2_2") (pintype "passive"))
      (node (ref "U9") (pin "5") (pintype "passive"))
    )
    (net (code "65") (name "Net-(R67-Pad2)") (class "Default")
      (node (ref "R67") (pin "2") (pinfunction "2_2") (pintype "passive"))
      (node (ref "U9") (pin "7") (pintype "passive"))
    )
    (net (code "66") (name "Net-(R70-Pad2)") (class "Default")
      (node (ref "R70") (pin "2") (pinfunction "2_2") (pintype "passive"))
      (node (ref "U10") (pin "2") (pintype "passive"))
    )
    (net (code "67") (name "Net-(R78-Pad1)") (class "Default")
      (node (ref "R78") (pin "1") (pinfunction "1_1") (pintype "passive"))
      (node (ref "U11") (pin "1") (pintype "passive"))
    )
    (net (code "68") (name "Net-(R79-Pad1)") (class "Default")
      (node (ref "R79") (pin "1") (pinfunction "1_1") (pintype "passive"))
      (node (ref "U11") (pin "3") (pintype "passive"))
    )
    (net (code "69") (name "Net-(R80-Pad1)") (class "Default")
      (node (ref "R80") (pin "1") (pinfunction "1_1") (pintype "passive"))
      (node (ref "U11") (pin "5") (pintype "passive"))
    )
    (net (code "70") (name "Net-(R81-Pad1)") (class "Default")
      (node (ref "R81") (pin "1") (pinfunction "1_1") (pintype "passive"))
      (node (ref "U11") (pin "7") (pintype "passive"))
    )
    (net (code "71") (name "unconnected-(DA12-NC-Pad5)") (class "Default")
      (node (ref "DA12") (pin "5") (pinfunction "NC_5") (pintype "passive"))
    )
    (net (code "72") (name "unconnected-(DA12-NC-Pad8)") (class "Default")
      (node (ref "DA12") (pin "8") (pinfunction "NC_8") (pintype "passive"))
    )
    (net (code "73") (name "unconnected-(DA12-ON{slash}OFF-Pad3)") (class "Default")
      (node (ref "DA12") (pin "3") (pinfunction "ON/OFF_3") (pintype "passive"))
    )
    (net (code "74") (name "unconnected-(DD13-NC-Pad7)") (class "Default")
      (node (ref "DD13") (pin "7") (pinfunction "NC_7") (pintype "passive"))
    )
    (net (code "75") (name "unconnected-(U10-Pad7)") (class "Default")
      (node (ref "U10") (pin "7") (pintype "passive"))
    )
    (net (code "76") (name "unconnected-(U10-Pad8)") (class "Default")
      (node (ref "U10") (pin "8") (pintype "passive"))
    )
  )
)
